# STM32.net
KiCad netlist of a schematic drawn in Altium Designer
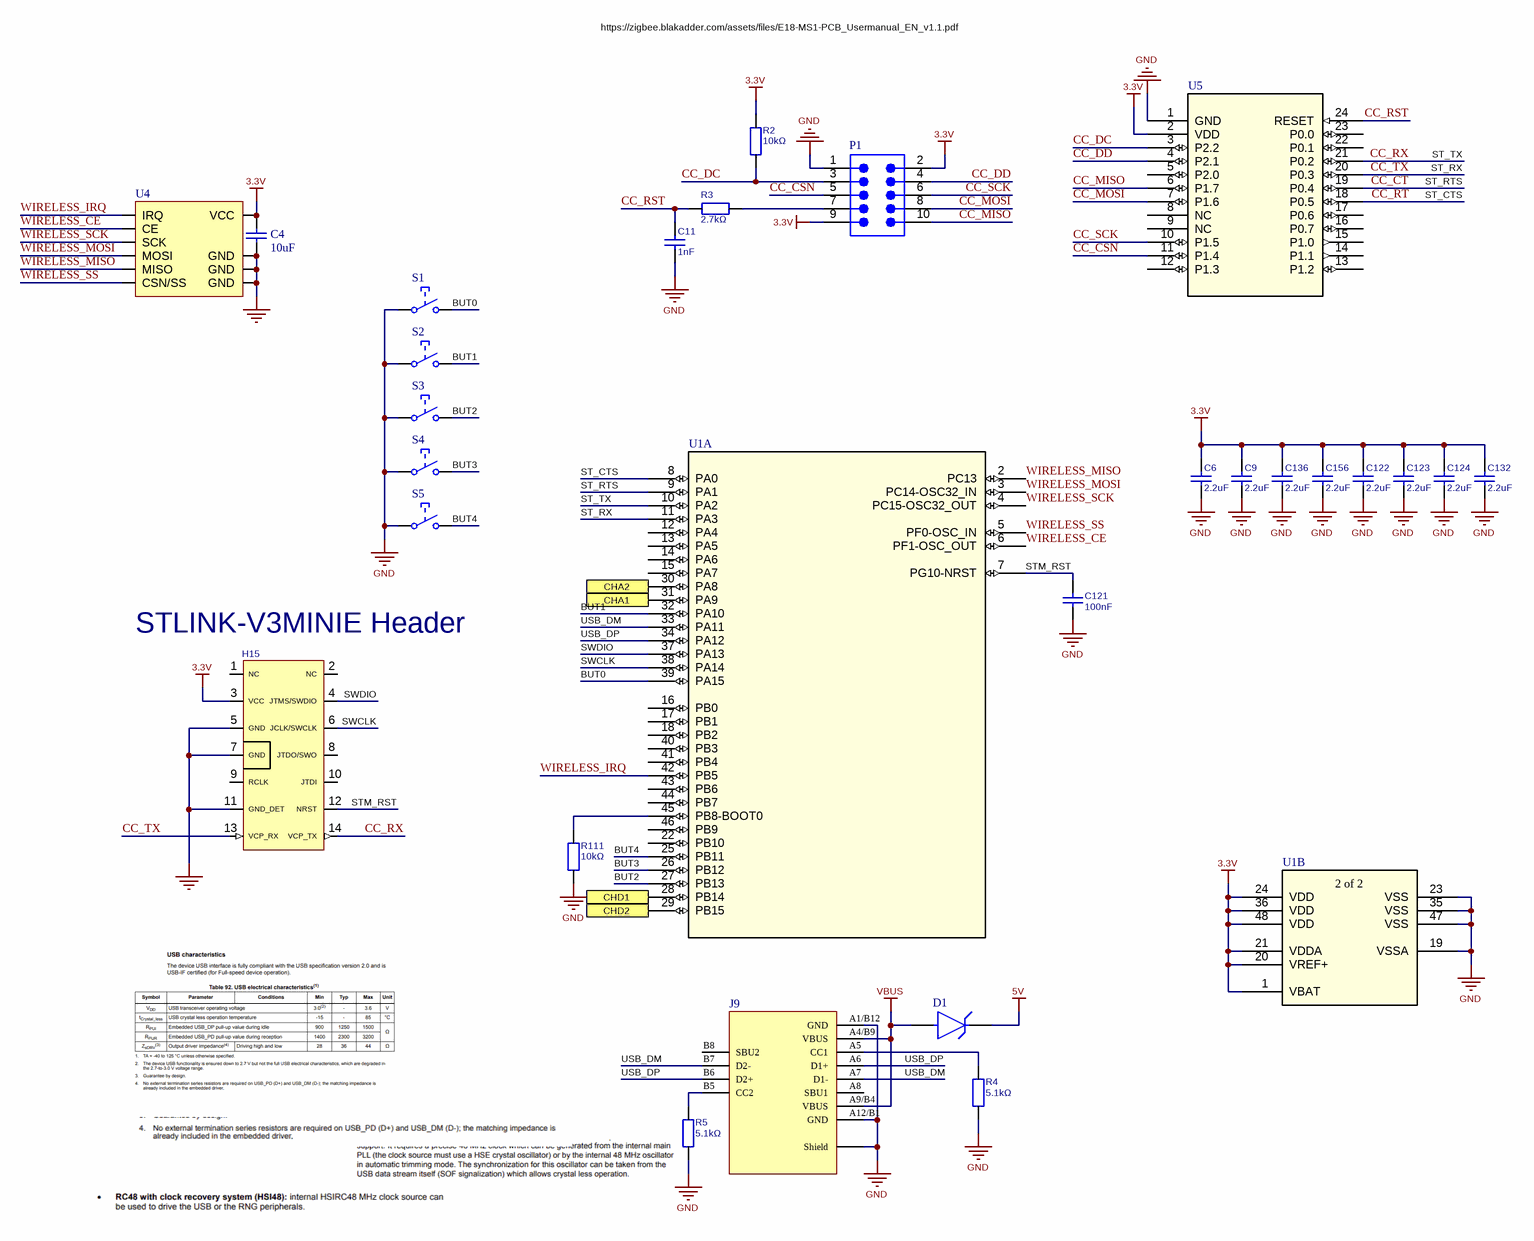
[diagram p0: STM32.SchDoc]

(export (version "E")
  (design (tool "Eeschema 10.0.6"))
  (components
    (comp (ref "C4")
      (value "10uF")
      (footprint "CAPC1608X08N")
      (libsource (lib "SchematicLibrary") (part "SMD_Cap"))
    )
    (comp (ref "C6")
      (value "2.2uF")
      (footprint "CAPC1005X05N")
      (libsource (lib "SchematicLibrary") (part "SMD_Cap"))
    )
    (comp (ref "C9")
      (value "2.2uF")
      (footprint "CAPC1005X05N")
      (libsource (lib "SchematicLibrary") (part "SMD_Cap"))
    )
    (comp (ref "C11")
      (value "1nF")
      (footprint "CAPC1005X05N")
      (libsource (lib "SchematicLibrary") (part "SMD_Cap"))
    )
    (comp (ref "C121")
      (value "100nF")
      (footprint "CAPC1005X05N")
      (fields
        (field (name "TOLERANCE") "±10%")
        (field (name "MANUFACTURER") "Samsung")
        (field (name "MPN") "CL05B104KB54PNC")
      )
      (libsource (lib "SchematicLibrary") (part "SMD_Cap"))
    )
    (comp (ref "C122")
      (value "2.2uF")
      (footprint "CAPC1005X05N")
      (libsource (lib "SchematicLibrary") (part "SMD_Cap"))
    )
    (comp (ref "C123")
      (value "2.2uF")
      (footprint "CAPC1005X05N")
      (libsource (lib "SchematicLibrary") (part "SMD_Cap"))
    )
    (comp (ref "C124")
      (value "2.2uF")
      (footprint "CAPC1005X05N")
      (libsource (lib "SchematicLibrary") (part "SMD_Cap"))
    )
    (comp (ref "C132")
      (value "2.2uF")
      (footprint "CAPC1005X05N")
      (libsource (lib "SchematicLibrary") (part "SMD_Cap"))
    )
    (comp (ref "C136")
      (value "2.2uF")
      (footprint "CAPC1005X05N")
      (libsource (lib "SchematicLibrary") (part "SMD_Cap"))
    )
    (comp (ref "C156")
      (value "2.2uF")
      (footprint "CAPC1005X05N")
      (libsource (lib "SchematicLibrary") (part "SMD_Cap"))
    )
    (comp (ref "D1")
      (value "~")
      (footprint "SOD123")
      (description "BZT52C20-7-F BZT52C20 Series 20 V 10 mA 500 mW Surface Mount Zener Diode - SOD-123")
      (fields (field (name "MPN") "B5819W SL") (field (name "JLCPCB PART #") "C8598"))
      (libsource (lib "Miscellaneous Devices") (part "f813f71cba58e380607f5dd3caf9714"))
    )
    (comp (ref "H15")
      (value "~")
      (footprint "Header 2x7 [14] 1.27mm Male TH")
      (fields (field (name "MPN") "DW127R-22-14-23"))
      (libsource (lib "Redako") (part "STLINK-V3MINIE_14P_TH"))
    )
    (comp (ref "J9")
      (value "~")
      (footprint "USB4105-GF-A-Footprint-1")
      (description "USB C USB4105-GF-A-120")
      (fields (field (name "MANUFACTURER") "Sofng") (field (name "JLCPCB PART #") "C136423"))
      (libsource (lib "RedakoJLC") (part "USB C USB4105-GF-A-120"))
    )
    (comp (ref "P1")
      (value "~")
      (footprint "62201021121")
      (fields (field (name "MPN") "1271WV-2x5P"))
      (libsource (lib "Altium Content Vault") (part "Header_Male_2R_10P"))
    )
    (comp (ref "R2")
      (value "10kΩ")
      (footprint "RESC1005X04N")
      (fields
        (field (name "TOLERANCE") "±1%")
        (field (name "MPN") "0402WGF1002TCE")
        (field (name "MANUFACTURER") "Uniroyal")
      )
      (libsource (lib "SchematicLibrary") (part "Res"))
    )
    (comp (ref "R3")
      (value "2.7kΩ")
      (footprint "RESC1005X04N")
      (fields (field (name "TOLERANCE") "±1%") (field (name "MANUFACTURER") "Uniroyal"))
      (libsource (lib "SchematicLibrary") (part "Res"))
    )
    (comp (ref "R4")
      (value "5.1kΩ")
      (footprint "RESC1005X04N")
      (fields (field (name "TOLERANCE") "±1%") (field (name "MANUFACTURER") "Uniroyal"))
      (libsource (lib "SchematicLibrary") (part "Res"))
    )
    (comp (ref "R5")
      (value "5.1kΩ")
      (footprint "RESC1005X04N")
      (fields (field (name "TOLERANCE") "±1%") (field (name "MANUFACTURER") "Uniroyal"))
      (libsource (lib "SchematicLibrary") (part "Res"))
    )
    (comp (ref "R111")
      (value "10kΩ")
      (footprint "RESC1005X04N")
      (fields
        (field (name "TOLERANCE") "±1%")
        (field (name "MPN") "0402WGF1002TCE")
        (field (name "MANUFACTURER") "Uniroyal")
      )
      (libsource (lib "SchematicLibrary") (part "Res"))
    )
    (comp (ref "S1")
      (value "~")
      (footprint "SWITCH - 4x3 SMD - 2 pin")
      (description "SPST 50MA @ 12VDC VERTICAL ROUND BUTTON 260GF SMD,3X4X2.0MM TACTILE SWITCHES ROHS")
      (fields (field (name "MPN") "TS-1088R-02026") (field (name "MANUFACTURER") "XUNPU"))
      (libsource (lib "RedakoJLC") (part "TS-1088R-02026"))
    )
    (comp (ref "S2")
      (value "~")
      (footprint "SWITCH - 4x3 SMD - 2 pin")
      (description "SPST 50MA @ 12VDC VERTICAL ROUND BUTTON 260GF SMD,3X4X2.0MM TACTILE SWITCHES ROHS")
      (fields (field (name "MPN") "TS-1088R-02026") (field (name "MANUFACTURER") "XUNPU"))
      (libsource (lib "RedakoJLC") (part "TS-1088R-02026"))
    )
    (comp (ref "S3")
      (value "~")
      (footprint "SWITCH - 4x3 SMD - 2 pin")
      (description "SPST 50MA @ 12VDC VERTICAL ROUND BUTTON 260GF SMD,3X4X2.0MM TACTILE SWITCHES ROHS")
      (fields (field (name "MPN") "TS-1088R-02026") (field (name "MANUFACTURER") "XUNPU"))
      (libsource (lib "RedakoJLC") (part "TS-1088R-02026"))
    )
    (comp (ref "S4")
      (value "~")
      (footprint "SWITCH - 4x3 SMD - 2 pin")
      (description "SPST 50MA @ 12VDC VERTICAL ROUND BUTTON 260GF SMD,3X4X2.0MM TACTILE SWITCHES ROHS")
      (fields (field (name "MPN") "TS-1088R-02026") (field (name "MANUFACTURER") "XUNPU"))
      (libsource (lib "RedakoJLC") (part "TS-1088R-02026"))
    )
    (comp (ref "S5")
      (value "~")
      (footprint "SWITCH - 4x3 SMD - 2 pin")
      (description "SPST 50MA @ 12VDC VERTICAL ROUND BUTTON 260GF SMD,3X4X2.0MM TACTILE SWITCHES ROHS")
      (fields (field (name "MPN") "TS-1088R-02026") (field (name "MANUFACTURER") "XUNPU"))
      (libsource (lib "RedakoJLC") (part "TS-1088R-02026"))
    )
    (comp (ref "U1")
      (value "~")
      (footprint "LQFP48-7x7mm")
      (description "No Description Available")
      (fields (field (name "MPN") "STM32G474CBT6TR"))
      (libsource (lib "Redako") (part "STM32G474CBT6TR"))
    )
    (comp (ref "U4")
      (value "~")
      (footprint "E01-2G4M13S")
      (fields (field (name "MPN") "E01-2G4M13S"))
      (libsource (lib "SchematicLibrary") (part "E01-ML01SP4"))
    )
    (comp (ref "U5")
      (value "~")
      (footprint "E18-MS1-PCB_BYT")
      (description "No Description Available")
      (fields (field (name "MPN") "E18-MS1-PCB"))
      (libsource (lib "E18-MS1-PCB") (part "E18-MS1-PCB"))
    )
  )
  (nets
    (net (code "1") (name "/BUT0") (class "Default")
      (node (ref "S1") (pin "2") (pintype "passive"))
      (node (ref "U1") (pin "39") (pinfunction "PA15_39") (pintype "bidirectional"))
    )
    (net (code "2") (name "/BUT1") (class "Default")
      (node (ref "S2") (pin "2") (pintype "passive"))
      (node (ref "U1") (pin "32") (pinfunction "PA10_32") (pintype "bidirectional"))
    )
    (net (code "3") (name "/BUT2") (class "Default")
      (node (ref "S3") (pin "2") (pintype "passive"))
      (node (ref "U1") (pin "27") (pinfunction "PB13_27") (pintype "bidirectional"))
    )
    (net (code "4") (name "/BUT3") (class "Default")
      (node (ref "S4") (pin "2") (pintype "passive"))
      (node (ref "U1") (pin "26") (pinfunction "PB12_26") (pintype "bidirectional"))
    )
    (net (code "5") (name "/BUT4") (class "Default")
      (node (ref "S5") (pin "2") (pintype "passive"))
      (node (ref "U1") (pin "25") (pinfunction "PB11_25") (pintype "bidirectional"))
    )
    (net (code "6") (name "/CC_CSN") (class "Default")
      (node (ref "P1") (pin "5") (pinfunction "5_5") (pintype "passive"))
      (node (ref "U5") (pin "11") (pinfunction "P1.4_11") (pintype "bidirectional"))
    )
    (net (code "7") (name "/CC_CT") (class "Default")
      (node (ref "U1") (pin "9") (pinfunction "PA1_9") (pintype "bidirectional"))
      (node (ref "U5") (pin "19") (pinfunction "P0.4_19") (pintype "bidirectional"))
    )
    (net (code "8") (name "/CC_DC") (class "Default")
      (node (ref "P1") (pin "3") (pinfunction "3_3") (pintype "passive"))
      (node (ref "R2") (pin "2") (pintype "passive"))
      (node (ref "U5") (pin "3") (pinfunction "P2.2_3") (pintype "bidirectional"))
    )
    (net (code "9") (name "/CC_DD") (class "Default")
      (node (ref "P1") (pin "4") (pinfunction "4_4") (pintype "passive"))
      (node (ref "U5") (pin "4") (pinfunction "P2.1_4") (pintype "bidirectional"))
    )
    (net (code "10") (name "/CC_MISO") (class "Default")
      (node (ref "P1") (pin "10") (pinfunction "10_10") (pintype "passive"))
      (node (ref "U5") (pin "6") (pinfunction "P1.7_6") (pintype "bidirectional"))
    )
    (net (code "11") (name "/CC_MOSI") (class "Default")
      (node (ref "P1") (pin "8") (pinfunction "8_8") (pintype "passive"))
      (node (ref "U5") (pin "7") (pinfunction "P1.6_7") (pintype "bidirectional"))
    )
    (net (code "12") (name "/CC_RST") (class "Default")
      (node (ref "C11") (pin "2") (pintype "passive"))
      (node (ref "R3") (pin "2") (pintype "passive"))
      (node (ref "U5") (pin "24") (pinfunction "RESET_24") (pintype "input"))
    )
    (net (code "13") (name "/CC_RT") (class "Default")
      (node (ref "U1") (pin "8") (pinfunction "PA0_8") (pintype "bidirectional"))
      (node (ref "U5") (pin "18") (pinfunction "P0.5_18") (pintype "bidirectional"))
    )
    (net (code "14") (name "/CC_RX") (class "Default")
      (node (ref "H15") (pin "14") (pinfunction "VCP_TX_14") (pintype "output"))
      (node (ref "U1") (pin "10") (pinfunction "PA2_10") (pintype "bidirectional"))
      (node (ref "U5") (pin "21") (pinfunction "P0.2_21") (pintype "bidirectional"))
    )
    (net (code "15") (name "/CC_SCK") (class "Default")
      (node (ref "P1") (pin "6") (pinfunction "6_6") (pintype "passive"))
      (node (ref "U5") (pin "10") (pinfunction "P1.5_10") (pintype "bidirectional"))
    )
    (net (code "16") (name "/CC_TX") (class "Default")
      (node (ref "H15") (pin "13") (pinfunction "VCP_RX_13") (pintype "input"))
      (node (ref "U1") (pin "11") (pinfunction "PA3_11") (pintype "bidirectional"))
      (node (ref "U5") (pin "20") (pinfunction "P0.3_20") (pintype "bidirectional"))
    )
    (net (code "17") (name "/CHA1") (class "Default")
      (node (ref "U1") (pin "31") (pinfunction "PA9_31") (pintype "bidirectional"))
    )
    (net (code "18") (name "/CHA2") (class "Default")
      (node (ref "U1") (pin "30") (pinfunction "PA8_30") (pintype "bidirectional"))
    )
    (net (code "19") (name "/CHD1") (class "Default")
      (node (ref "U1") (pin "28") (pinfunction "PB14_28") (pintype "bidirectional"))
    )
    (net (code "20") (name "/CHD2") (class "Default")
      (node (ref "U1") (pin "29") (pinfunction "PB15_29") (pintype "bidirectional"))
    )
    (net (code "21") (name "/STM_RST") (class "Default")
      (node (ref "C121") (pin "2") (pintype "passive"))
      (node (ref "H15") (pin "12") (pinfunction "NRST_12") (pintype "passive"))
      (node (ref "U1") (pin "7") (pinfunction "PG10-NRST_7") (pintype "bidirectional"))
    )
    (net (code "22") (name "/SWCLK") (class "Default")
      (node (ref "H15") (pin "6") (pinfunction "JCLK/SWCLK_6") (pintype "passive"))
      (node (ref "U1") (pin "38") (pinfunction "PA14_38") (pintype "bidirectional"))
    )
    (net (code "23") (name "/SWDIO") (class "Default")
      (node (ref "H15") (pin "4") (pinfunction "JTMS/SWDIO_4") (pintype "passive"))
      (node (ref "U1") (pin "37") (pinfunction "PA13_37") (pintype "bidirectional"))
    )
    (net (code "24") (name "/USB_DM") (class "Default")
      (node (ref "J9") (pin "A7") (pinfunction "D1-_A7") (pintype "passive"))
      (node (ref "J9") (pin "B7") (pinfunction "D2-_B7") (pintype "passive"))
      (node (ref "U1") (pin "33") (pinfunction "PA11_33") (pintype "bidirectional"))
    )
    (net (code "25") (name "/USB_DP") (class "Default")
      (node (ref "J9") (pin "A6") (pinfunction "D1+_A6") (pintype "passive"))
      (node (ref "J9") (pin "B6") (pinfunction "D2+_B6") (pintype "passive"))
      (node (ref "U1") (pin "34") (pinfunction "PA12_34") (pintype "bidirectional"))
    )
    (net (code "26") (name "/WIRELESS_CE") (class "Default")
      (node (ref "U1") (pin "6") (pinfunction "PF1-OSC_OUT_6") (pintype "bidirectional"))
      (node (ref "U4") (pin "2") (pinfunction "CE_2") (pintype "passive"))
    )
    (net (code "27") (name "/WIRELESS_IRQ") (class "Default")
      (node (ref "U1") (pin "42") (pinfunction "PB5_42") (pintype "bidirectional"))
      (node (ref "U4") (pin "7") (pinfunction "IRQ_7") (pintype "passive"))
    )
    (net (code "28") (name "/WIRELESS_MISO") (class "Default")
      (node (ref "U1") (pin "2") (pinfunction "PC13_2") (pintype "bidirectional"))
      (node (ref "U4") (pin "6") (pinfunction "MISO_6") (pintype "passive"))
    )
    (net (code "29") (name "/WIRELESS_MOSI") (class "Default")
      (node (ref "U1") (pin "3") (pinfunction "PC14-OSC32_IN_3") (pintype "bidirectional"))
      (node (ref "U4") (pin "5") (pinfunction "MOSI_5") (pintype "passive"))
    )
    (net (code "30") (name "/WIRELESS_SCK") (class "Default")
      (node (ref "U1") (pin "4") (pinfunction "PC15-OSC32_OUT_4") (pintype "bidirectional"))
      (node (ref "U4") (pin "4") (pinfunction "SCK_4") (pintype "passive"))
    )
    (net (code "31") (name "/WIRELESS_SS") (class "Default")
      (node (ref "U1") (pin "5") (pinfunction "PF0-OSC_IN_5") (pintype "bidirectional"))
      (node (ref "U4") (pin "3") (pinfunction "CSN/SS_3") (pintype "passive"))
    )
    (net (code "32") (name "3.3V") (class "Default")
      (node (ref "C122") (pin "2") (pintype "passive"))
      (node (ref "C123") (pin "2") (pintype "passive"))
      (node (ref "C124") (pin "2") (pintype "passive"))
      (node (ref "C132") (pin "2") (pintype "passive"))
      (node (ref "C136") (pin "2") (pintype "passive"))
      (node (ref "C156") (pin "2") (pintype "passive"))
      (node (ref "C4") (pin "1") (pintype "passive"))
      (node (ref "C6") (pin "2") (pintype "passive"))
      (node (ref "C9") (pin "2") (pintype "passive"))
      (node (ref "H15") (pin "3") (pinfunction "VCC_3") (pintype "passive"))
      (node (ref "P1") (pin "2") (pinfunction "2_2") (pintype "passive"))
      (node (ref "P1") (pin "9") (pinfunction "9_9") (pintype "passive"))
      (node (ref "R2") (pin "1") (pintype "passive"))
      (node (ref "U1") (pin "1") (pinfunction "VBAT_1") (pintype "power_in"))
      (node (ref "U1") (pin "20") (pinfunction "VREF+_20") (pintype "power_in"))
      (node (ref "U1") (pin "21") (pinfunction "VDDA_21") (pintype "power_in"))
      (node (ref "U1") (pin "24") (pinfunction "VDD_24") (pintype "power_in"))
      (node (ref "U1") (pin "36") (pinfunction "VDD_36") (pintype "power_in"))
      (node (ref "U1") (pin "48") (pinfunction "VDD_48") (pintype "power_in"))
      (node (ref "U4") (pin "1") (pinfunction "VCC_1") (pintype "passive"))
      (node (ref "U5") (pin "2") (pinfunction "VDD_2") (pintype "power_in"))
    )
    (net (code "33") (name "5V") (class "Default")
      (node (ref "D1") (pin "2") (pinfunction "C_2") (pintype "passive"))
    )
    (net (code "34") (name "GND") (class "Default")
      (node (ref "C11") (pin "1") (pintype "passive"))
      (node (ref "C121") (pin "1") (pintype "passive"))
      (node (ref "C122") (pin "1") (pintype "passive"))
      (node (ref "C123") (pin "1") (pintype "passive"))
      (node (ref "C124") (pin "1") (pintype "passive"))
      (node (ref "C132") (pin "1") (pintype "passive"))
      (node (ref "C136") (pin "1") (pintype "passive"))
      (node (ref "C156") (pin "1") (pintype "passive"))
      (node (ref "C4") (pin "2") (pintype "passive"))
      (node (ref "C6") (pin "1") (pintype "passive"))
      (node (ref "C9") (pin "1") (pintype "passive"))
      (node (ref "H15") (pin "11") (pinfunction "GND_DET_11") (pintype "passive"))
      (node (ref "H15") (pin "5") (pinfunction "GND_5") (pintype "passive"))
      (node (ref "H15") (pin "7") (pinfunction "GND_7") (pintype "passive"))
      (node (ref "J9") (pin "A1/B12") (pinfunction "GND_A1/B12") (pintype "passive"))
      (node (ref "J9") (pin "A12/B1") (pinfunction "GND_A12/B1") (pintype "passive"))
      (node (ref "J9") (pin "MNT") (pinfunction "Shield_MNT") (pintype "passive"))
      (node (ref "P1") (pin "1") (pinfunction "1_1") (pintype "passive"))
      (node (ref "R111") (pin "2") (pintype "passive"))
      (node (ref "R4") (pin "2") (pintype "passive"))
      (node (ref "R5") (pin "2") (pintype "passive"))
      (node (ref "S1") (pin "1") (pintype "passive"))
      (node (ref "S2") (pin "1") (pintype "passive"))
      (node (ref "S3") (pin "1") (pintype "passive"))
      (node (ref "S4") (pin "1") (pintype "passive"))
      (node (ref "S5") (pin "1") (pintype "passive"))
      (node (ref "U1") (pin "19") (pinfunction "VSSA_19") (pintype "power_in"))
      (node (ref "U1") (pin "23") (pinfunction "VSS_23") (pintype "power_in"))
      (node (ref "U1") (pin "35") (pinfunction "VSS_35") (pintype "power_in"))
      (node (ref "U1") (pin "47") (pinfunction "VSS_47") (pintype "power_in"))
      (node (ref "U4") (pin "10") (pinfunction "GND_10") (pintype "passive"))
      (node (ref "U4") (pin "8") (pinfunction "GND_8") (pintype "passive"))
      (node (ref "U4") (pin "9") (pinfunction "GND_9") (pintype "passive"))
      (node (ref "U5") (pin "1") (pinfunction "GND_1") (pintype "power_in"))
    )
    (net (code "35") (name "Net-(J9-CC1)") (class "Default")
      (node (ref "J9") (pin "A5") (pinfunction "CC1_A5") (pintype "passive"))
      (node (ref "R4") (pin "1") (pintype "passive"))
    )
    (net (code "36") (name "Net-(J9-CC2)") (class "Default")
      (node (ref "J9") (pin "B5") (pinfunction "CC2_B5") (pintype "passive"))
      (node (ref "R5") (pin "1") (pintype "passive"))
    )
    (net (code "37") (name "Net-(P1-Pad7)") (class "Default")
      (node (ref "P1") (pin "7") (pinfunction "7_7") (pintype "passive"))
      (node (ref "R3") (pin "1") (pintype "passive"))
    )
    (net (code "38") (name "Net-(U1A-PB8-BOOT0)") (class "Default")
      (node (ref "R111") (pin "1") (pintype "passive"))
      (node (ref "U1") (pin "45") (pinfunction "PB8-BOOT0_45") (pintype "bidirectional"))
    )
    (net (code "39") (name "VBUS") (class "Default")
      (node (ref "D1") (pin "1") (pinfunction "A_1") (pintype "passive"))
      (node (ref "J9") (pin "A4/B9") (pinfunction "VBUS_A4/B9") (pintype "passive"))
      (node (ref "J9") (pin "A9/B4") (pinfunction "VBUS_A9/B4") (pintype "passive"))
    )
    (net (code "40") (name "unconnected-(H15-JTDI-Pad10)") (class "Default")
      (node (ref "H15") (pin "10") (pinfunction "JTDI_10") (pintype "passive"))
    )
    (net (code "41") (name "unconnected-(H15-JTDO{slash}SWO-Pad8)") (class "Default")
      (node (ref "H15") (pin "8") (pinfunction "JTDO/SWO_8") (pintype "passive"))
    )
    (net (code "42") (name "unconnected-(H15-NC-Pad1)") (class "Default")
      (node (ref "H15") (pin "1") (pinfunction "NC_1") (pintype "passive"))
    )
    (net (code "43") (name "unconnected-(H15-NC-Pad2)") (class "Default")
      (node (ref "H15") (pin "2") (pinfunction "NC_2") (pintype "passive"))
    )
    (net (code "44") (name "unconnected-(H15-RCLK-Pad9)") (class "Default")
      (node (ref "H15") (pin "9") (pinfunction "RCLK_9") (pintype "passive"))
    )
    (net (code "45") (name "unconnected-(J9-SBU1-PadA8)") (class "Default")
      (node (ref "J9") (pin "A8") (pinfunction "SBU1_A8") (pintype "passive"))
    )
    (net (code "46") (name "unconnected-(J9-SBU2-PadB8)") (class "Default")
      (node (ref "J9") (pin "B8") (pinfunction "SBU2_B8") (pintype "passive"))
    )
    (net (code "47") (name "unconnected-(U1A-PA4-Pad12)") (class "Default")
      (node (ref "U1") (pin "12") (pinfunction "PA4_12") (pintype "bidirectional"))
    )
    (net (code "48") (name "unconnected-(U1A-PA5-Pad13)") (class "Default")
      (node (ref "U1") (pin "13") (pinfunction "PA5_13") (pintype "bidirectional"))
    )
    (net (code "49") (name "unconnected-(U1A-PA6-Pad14)") (class "Default")
      (node (ref "U1") (pin "14") (pinfunction "PA6_14") (pintype "bidirectional"))
    )
    (net (code "50") (name "unconnected-(U1A-PA7-Pad15)") (class "Default")
      (node (ref "U1") (pin "15") (pinfunction "PA7_15") (pintype "bidirectional"))
    )
    (net (code "51") (name "unconnected-(U1A-PB0-Pad16)") (class "Default")
      (node (ref "U1") (pin "16") (pinfunction "PB0_16") (pintype "bidirectional"))
    )
    (net (code "52") (name "unconnected-(U1A-PB1-Pad17)") (class "Default")
      (node (ref "U1") (pin "17") (pinfunction "PB1_17") (pintype "bidirectional"))
    )
    (net (code "53") (name "unconnected-(U1A-PB2-Pad18)") (class "Default")
      (node (ref "U1") (pin "18") (pinfunction "PB2_18") (pintype "bidirectional"))
    )
    (net (code "54") (name "unconnected-(U1A-PB3-Pad40)") (class "Default")
      (node (ref "U1") (pin "40") (pinfunction "PB3_40") (pintype "bidirectional"))
    )
    (net (code "55") (name "unconnected-(U1A-PB4-Pad41)") (class "Default")
      (node (ref "U1") (pin "41") (pinfunction "PB4_41") (pintype "bidirectional"))
    )
    (net (code "56") (name "unconnected-(U1A-PB6-Pad43)") (class "Default")
      (node (ref "U1") (pin "43") (pinfunction "PB6_43") (pintype "bidirectional"))
    )
    (net (code "57") (name "unconnected-(U1A-PB7-Pad44)") (class "Default")
      (node (ref "U1") (pin "44") (pinfunction "PB7_44") (pintype "bidirectional"))
    )
    (net (code "58") (name "unconnected-(U1A-PB9-Pad46)") (class "Default")
      (node (ref "U1") (pin "46") (pinfunction "PB9_46") (pintype "bidirectional"))
    )
    (net (code "59") (name "unconnected-(U1A-PB10-Pad22)") (class "Default")
      (node (ref "U1") (pin "22") (pinfunction "PB10_22") (pintype "bidirectional"))
    )
    (net (code "60") (name "unconnected-(U5-NC-Pad8)") (class "Default")
      (node (ref "U5") (pin "8") (pinfunction "NC_8") (pintype "passive"))
    )
    (net (code "61") (name "unconnected-(U5-NC-Pad9)") (class "Default")
      (node (ref "U5") (pin "9") (pinfunction "NC_9") (pintype "passive"))
    )
    (net (code "62") (name "unconnected-(U5-P0.0-Pad23)") (class "Default")
      (node (ref "U5") (pin "23") (pinfunction "P0.0_23") (pintype "bidirectional"))
    )
    (net (code "63") (name "unconnected-(U5-P0.1-Pad22)") (class "Default")
      (node (ref "U5") (pin "22") (pinfunction "P0.1_22") (pintype "bidirectional"))
    )
    (net (code "64") (name "unconnected-(U5-P0.6-Pad17)") (class "Default")
      (node (ref "U5") (pin "17") (pinfunction "P0.6_17") (pintype "bidirectional"))
    )
    (net (code "65") (name "unconnected-(U5-P0.7-Pad16)") (class "Default")
      (node (ref "U5") (pin "16") (pinfunction "P0.7_16") (pintype "bidirectional"))
    )
    (net (code "66") (name "unconnected-(U5-P1.0-Pad15)") (class "Default")
      (node (ref "U5") (pin "15") (pinfunction "P1.0_15") (pintype "output"))
    )
    (net (code "67") (name "unconnected-(U5-P1.1-Pad14)") (class "Default")
      (node (ref "U5") (pin "14") (pinfunction "P1.1_14") (pintype "output"))
    )
    (net (code "68") (name "unconnected-(U5-P1.2-Pad13)") (class "Default")
      (node (ref "U5") (pin "13") (pinfunction "P1.2_13") (pintype "bidirectional"))
    )
    (net (code "69") (name "unconnected-(U5-P1.3-Pad12)") (class "Default")
      (node (ref "U5") (pin "12") (pinfunction "P1.3_12") (pintype "bidirectional"))
    )
    (net (code "70") (name "unconnected-(U5-P2.0-Pad5)") (class "Default")
      (node (ref "U5") (pin "5") (pinfunction "P2.0_5") (pintype "bidirectional"))
    )
  )
)
